# V2_USB.net
KiCad netlist of a schematic drawn in Altium Designer
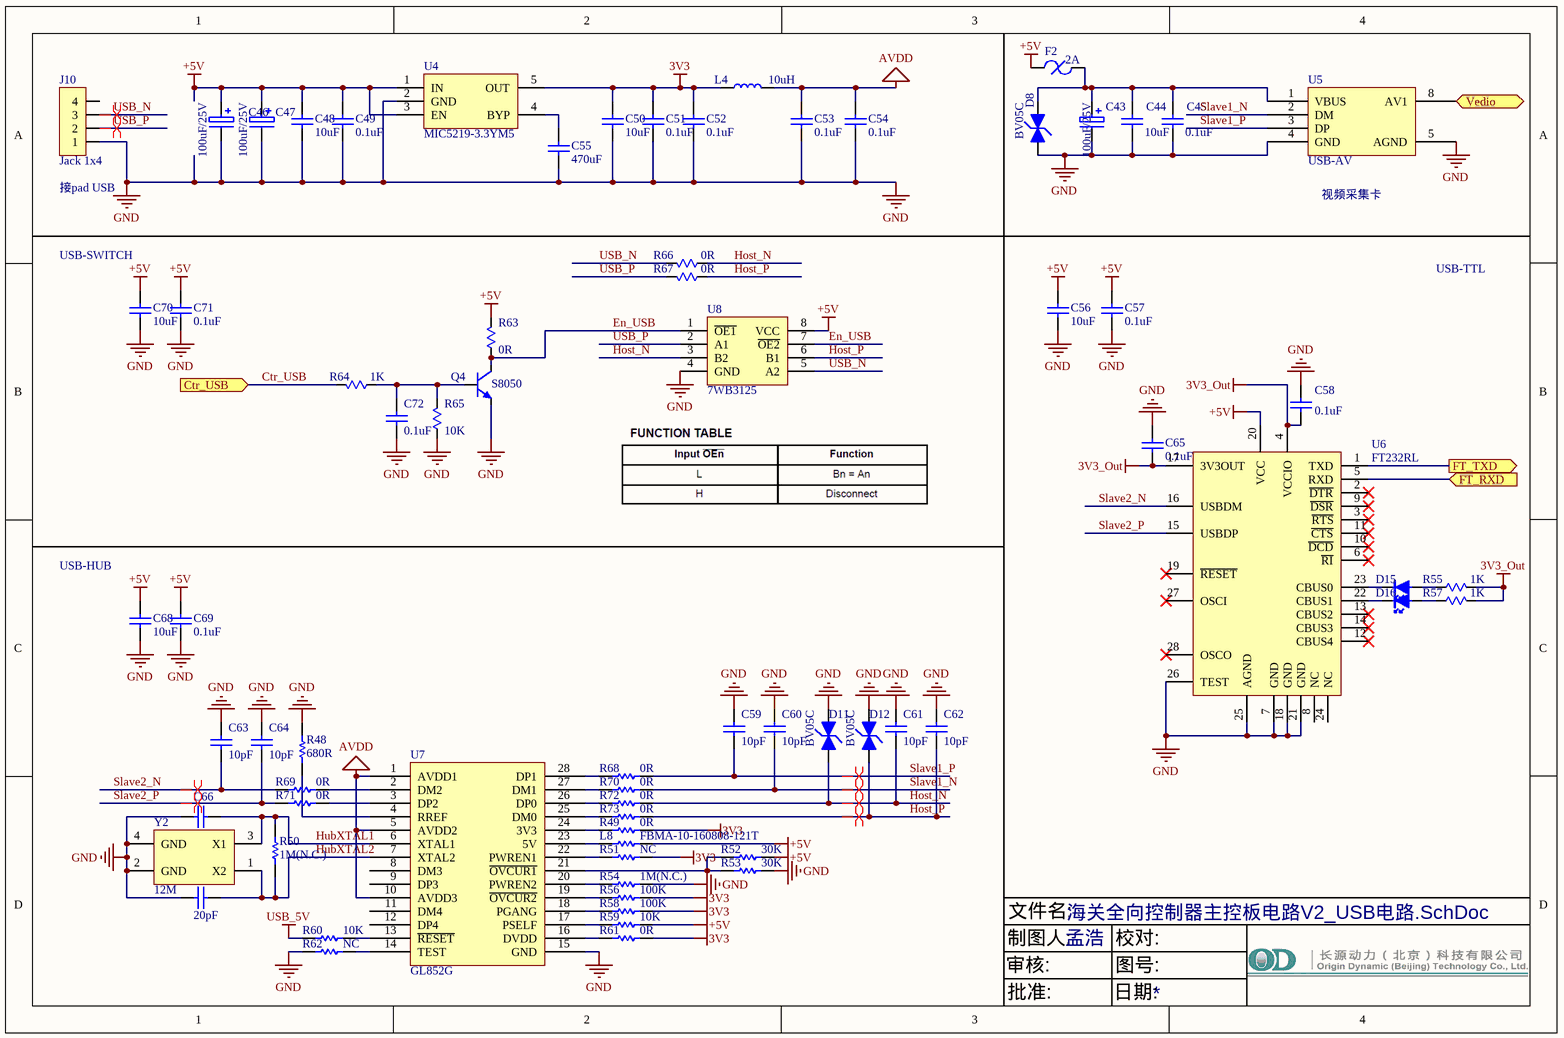
[diagram p0: 海关全向控制器主控板电路V2_USB电路.SchDoc]

(export (version "E")
  (design (tool "Eeschema 10.0.6"))
  (components
    (comp (ref "C43") (value "100uF/25V") (footprint "C7343") (libsource (lib "RLCYDF") (part "Cap Poll")))
    (comp (ref "C44")
      (value "10uF")
      (footprint "C0603")
      (description "CAP")
      (fields (field (name "PUBLISHER") "Altium Limited"))
      (libsource (lib "Passive Components Class") (part "CAP"))
    )
    (comp (ref "C45") (value "0.1uF") (footprint "C0603") (libsource (lib "SMD") (part "Cap Semi")))
    (comp (ref "C46") (value "100uF/25V") (footprint "C7343") (libsource (lib "RLCYDF") (part "Cap Poll")))
    (comp (ref "C47") (value "100uF/25V") (footprint "C7343") (libsource (lib "RLCYDF") (part "Cap Poll")))
    (comp (ref "C48")
      (value "10uF")
      (footprint "C0603")
      (description "CAP")
      (fields (field (name "PUBLISHER") "Altium Limited"))
      (libsource (lib "Passive Components Class") (part "CAP"))
    )
    (comp (ref "C49") (value "0.1uF") (footprint "C0603") (libsource (lib "SMD") (part "Cap Semi")))
    (comp (ref "C50")
      (value "10uF")
      (footprint "C0603")
      (description "CAP")
      (fields (field (name "PUBLISHER") "Altium Limited"))
      (libsource (lib "Passive Components Class") (part "CAP"))
    )
    (comp (ref "C51") (value "0.1uF") (footprint "C0603") (libsource (lib "SMD") (part "Cap Semi")))
    (comp (ref "C52") (value "0.1uF") (footprint "C0603") (libsource (lib "SMD") (part "Cap Semi")))
    (comp (ref "C53") (value "0.1uF") (footprint "C0603") (libsource (lib "SMD") (part "Cap Semi")))
    (comp (ref "C54") (value "0.1uF") (footprint "C0603") (libsource (lib "SMD") (part "Cap Semi")))
    (comp (ref "C55") (value "470uF") (footprint "C0603") (libsource (lib "SMD") (part "Cap Semi")))
    (comp (ref "C56")
      (value "10uF")
      (footprint "C0603")
      (description "CAP")
      (fields (field (name "PUBLISHER") "Altium Limited"))
      (libsource (lib "Passive Components Class") (part "CAP"))
    )
    (comp (ref "C57") (value "0.1uF") (footprint "C0603") (libsource (lib "SMD") (part "Cap Semi")))
    (comp (ref "C58")
      (value "0.1uF")
      (footprint "C0603")
      (description "Capacitor")
      (fields (field (name "PUBLISHER") "Altium Limited"))
      (libsource (lib "Miscellaneous Devices") (part "Cap"))
    )
    (comp (ref "C59") (value "10pF") (footprint "C0603") (libsource (lib "SMD") (part "Cap Semi")))
    (comp (ref "C60") (value "10pF") (footprint "C0603") (libsource (lib "SMD") (part "Cap Semi")))
    (comp (ref "C61") (value "10pF") (footprint "C0603") (libsource (lib "SMD") (part "Cap Semi")))
    (comp (ref "C62") (value "10pF") (footprint "C0603") (libsource (lib "SMD") (part "Cap Semi")))
    (comp (ref "C63") (value "10pF") (footprint "C0603") (libsource (lib "SMD") (part "Cap Semi")))
    (comp (ref "C64") (value "10pF") (footprint "C0603") (libsource (lib "SMD") (part "Cap Semi")))
    (comp (ref "C65") (value "0.1uF") (footprint "C0603") (libsource (lib "SMD") (part "Cap Semi")))
    (comp (ref "C66") (value "20pF") (footprint "C0603") (libsource (lib "SMD") (part "Cap Semi")))
    (comp (ref "C67") (value "20pF") (footprint "C0603") (libsource (lib "SMD") (part "Cap Semi")))
    (comp (ref "C68")
      (value "10uF")
      (footprint "C0603")
      (description "CAP")
      (fields (field (name "PUBLISHER") "Altium Limited"))
      (libsource (lib "Passive Components Class") (part "CAP"))
    )
    (comp (ref "C69") (value "0.1uF") (footprint "C0603") (libsource (lib "SMD") (part "Cap Semi")))
    (comp (ref "C70")
      (value "10uF")
      (footprint "C0603")
      (description "CAP")
      (fields (field (name "PUBLISHER") "Altium Limited"))
      (libsource (lib "Passive Components Class") (part "CAP"))
    )
    (comp (ref "C71") (value "0.1uF") (footprint "C0603") (libsource (lib "SMD") (part "Cap Semi")))
    (comp (ref "C72")
      (value "0.1uF")
      (footprint "C0603")
      (description "CAP")
      (fields (field (name "PUBLISHER") "Altium Limited"))
      (libsource (lib "Passive Components Class") (part "CAP"))
    )
    (comp (ref "D8") (value "BV05C") (footprint "SOD323") (libsource (lib "RLCYDF") (part "Diode-TVS")))
    (comp (ref "D11") (value "BV05C") (footprint "SOD323") (libsource (lib "RLCYDF") (part "Diode-TVS")))
    (comp (ref "D12") (value "BV05C") (footprint "SOD323") (libsource (lib "RLCYDF") (part "Diode-TVS")))
    (comp (ref "D15")
      (value "LED")
      (footprint "LED0603")
      (libsource (lib "Passive Components Class") (part "LED"))
    )
    (comp (ref "D16")
      (value "LED")
      (footprint "LED0603")
      (libsource (lib "Passive Components Class") (part "LED"))
    )
    (comp (ref "F2") (value "2A") (footprint "F1218") (libsource (lib "RLCYDF") (part "Fuse2")))
    (comp (ref "J10")
      (value "Jack 1x4")
      (footprint "ZH-4AWD")
      (description "插座")
      (libsource (lib "Connector") (part "Jack 1x4"))
    )
    (comp (ref "L4") (value "10uH") (footprint "L0603") (libsource (lib "RLCYDF") (part "Inductor")))
    (comp (ref "L8") (value "FBMA-10-160808-121T") (footprint "R0603") (libsource (lib "SMD") (part "Res")))
    (comp (ref "Q4")
      (value "S8050")
      (footprint "SOT-23")
      (description "NPN General Purpose Amplifier")
      (fields (field (name "PUBLISHER") "Altium Limited"))
      (libsource (lib "Bdmc4810") (part "NPN"))
    )
    (comp (ref "R48") (value "680R") (footprint "R0603") (libsource (lib "SMD") (part "Res")))
    (comp (ref "R49") (value "0R") (footprint "R0603") (libsource (lib "SMD") (part "Res")))
    (comp (ref "R50") (value "1M(N.C.)") (footprint "R0603") (libsource (lib "SMD") (part "Res")))
    (comp (ref "R51") (value "NC") (footprint "R0603") (libsource (lib "SMD") (part "Res")))
    (comp (ref "R52") (value "30K") (footprint "R0603") (libsource (lib "SMD") (part "Res")))
    (comp (ref "R53") (value "30K") (footprint "R0603") (libsource (lib "SMD") (part "Res")))
    (comp (ref "R54") (value "1M(N.C.)") (footprint "R0603") (libsource (lib "SMD") (part "Res")))
    (comp (ref "R55")
      (value "1K")
      (footprint "R0603")
      (description "Resistor")
      (fields (field (name "PUBLISHER") "Altium Limited"))
      (libsource (lib "Temp") (part "Res"))
    )
    (comp (ref "R56") (value "100K") (footprint "R0603") (libsource (lib "SMD") (part "Res")))
    (comp (ref "R57")
      (value "1K")
      (footprint "R0603")
      (description "Resistor")
      (fields (field (name "PUBLISHER") "Altium Limited"))
      (libsource (lib "Temp") (part "Res"))
    )
    (comp (ref "R58") (value "100K") (footprint "R0603") (libsource (lib "SMD") (part "Res")))
    (comp (ref "R59") (value "10K") (footprint "R0603") (libsource (lib "SMD") (part "Res")))
    (comp (ref "R60") (value "10K") (footprint "R0603") (libsource (lib "SMD") (part "Res")))
    (comp (ref "R61") (value "0R") (footprint "R0603") (libsource (lib "SMD") (part "Res")))
    (comp (ref "R62") (value "NC") (footprint "R0603") (libsource (lib "SMD") (part "Res")))
    (comp (ref "R63")
      (value "0R")
      (footprint "R0603")
      (description "Resistor")
      (fields (field (name "PUBLISHER") "Altium Limited"))
      (libsource (lib "Temp") (part "Res"))
    )
    (comp (ref "R64")
      (value "1K")
      (footprint "R0603")
      (description "Resistor")
      (fields (field (name "PUBLISHER") "Altium Limited"))
      (libsource (lib "Temp") (part "Res"))
    )
    (comp (ref "R65")
      (value "10K")
      (footprint "R0603")
      (description "Resistor")
      (fields (field (name "PUBLISHER") "Altium Limited"))
      (libsource (lib "Temp") (part "Res"))
    )
    (comp (ref "R66")
      (value "0R")
      (footprint "R0603")
      (description "Resistor")
      (fields (field (name "PUBLISHER") "Altium Limited"))
      (libsource (lib "Temp") (part "Res"))
    )
    (comp (ref "R67")
      (value "0R")
      (footprint "R0603")
      (description "Resistor")
      (fields (field (name "PUBLISHER") "Altium Limited"))
      (libsource (lib "Temp") (part "Res"))
    )
    (comp (ref "R68") (value "0R") (footprint "R0603") (libsource (lib "SMD") (part "Res")))
    (comp (ref "R69") (value "0R") (footprint "R0603") (libsource (lib "SMD") (part "Res")))
    (comp (ref "R70") (value "0R") (footprint "R0603") (libsource (lib "SMD") (part "Res")))
    (comp (ref "R71") (value "0R") (footprint "R0603") (libsource (lib "SMD") (part "Res")))
    (comp (ref "R72") (value "0R") (footprint "R0603") (libsource (lib "SMD") (part "Res")))
    (comp (ref "R73") (value "0R") (footprint "R0603") (libsource (lib "SMD") (part "Res")))
    (comp (ref "U4")
      (value "MIC5219-3.3YM5")
      (footprint "SOT-23-5")
      (libsource (lib "Power") (part "MIC5205"))
    )
    (comp (ref "U5") (value "USB-AV") (footprint "USB-AV") (libsource (lib "Module") (part "USB-AV")))
    (comp (ref "U6")
      (value "FT232RL")
      (footprint "SSOP-28")
      (libsource (lib "海关全向控制器主控板V2") (part "FT232RL"))
    )
    (comp (ref "U7")
      (value "GL852G")
      (footprint "SSOP-28")
      (description "USB 2.0 Low-Power HUB Controller")
      (libsource (lib "chip") (part "GL850G"))
    )
    (comp (ref "U8") (value "7WB3125") (footprint "Micro8") (libsource (lib "chip") (part "7WB3125")))
    (comp (ref "Y2") (value "12M") (footprint "XTAL3225") (libsource (lib "RLCYDF") (part "XTAL3225")))
  )
  (nets
    (net (code "1") (name "+5V") (class "Default")
      (node (ref "C46") (pin "1") (pinfunction "1_1") (pintype "passive"))
      (node (ref "C47") (pin "1") (pinfunction "1_1") (pintype "passive"))
      (node (ref "C48") (pin "1") (pinfunction "1_1") (pintype "passive"))
      (node (ref "C49") (pin "2") (pinfunction "2_2") (pintype "passive"))
      (node (ref "C56") (pin "1") (pinfunction "1_1") (pintype "passive"))
      (node (ref "C57") (pin "2") (pinfunction "2_2") (pintype "passive"))
      (node (ref "C68") (pin "1") (pinfunction "1_1") (pintype "passive"))
      (node (ref "C69") (pin "2") (pinfunction "2_2") (pintype "passive"))
      (node (ref "C70") (pin "1") (pinfunction "1_1") (pintype "passive"))
      (node (ref "C71") (pin "2") (pinfunction "2_2") (pintype "passive"))
      (node (ref "F2") (pin "1") (pinfunction "1_1") (pintype "passive"))
      (node (ref "L8") (pin "2") (pinfunction "2_2") (pintype "passive"))
      (node (ref "R52") (pin "1") (pinfunction "1_1") (pintype "passive"))
      (node (ref "R59") (pin "1") (pinfunction "1_1") (pintype "passive"))
      (node (ref "R63") (pin "1") (pinfunction "1_1") (pintype "passive"))
      (node (ref "U4") (pin "1") (pinfunction "IN_1") (pintype "passive"))
      (node (ref "U4") (pin "3") (pinfunction "EN_3") (pintype "passive"))
      (node (ref "U6") (pin "20") (pinfunction "VCC_20") (pintype "passive"))
      (node (ref "U8") (pin "8") (pinfunction "VCC_8") (pintype "passive"))
    )
    (net (code "2") (name "/Ctr_USB") (class "Default")
      (node (ref "R64") (pin "1") (pinfunction "1_1") (pintype "passive"))
    )
    (net (code "3") (name "/En_USB") (class "Default")
      (node (ref "Q4") (pin "3") (pinfunction "C_3") (pintype "passive"))
      (node (ref "R63") (pin "2") (pinfunction "2_2") (pintype "passive"))
      (node (ref "U8") (pin "1") (pinfunction "~{OE1}_1") (pintype "passive"))
      (node (ref "U8") (pin "7") (pinfunction "~{OE2}_7") (pintype "passive"))
    )
    (net (code "4") (name "/FT_RXD") (class "Default")
      (node (ref "U6") (pin "5") (pinfunction "RXD_5") (pintype "passive"))
    )
    (net (code "5") (name "/FT_TXD") (class "Default")
      (node (ref "U6") (pin "1") (pinfunction "TXD_1") (pintype "passive"))
    )
    (net (code "6") (name "/Host_N") (class "Default")
      (node (ref "C61") (pin "1") (pinfunction "1_1") (pintype "passive"))
      (node (ref "D11") (pin "2") (pinfunction "K_2") (pintype "passive"))
      (node (ref "R66") (pin "2") (pinfunction "2_2") (pintype "passive"))
      (node (ref "R72") (pin "1") (pinfunction "1_1") (pintype "passive"))
      (node (ref "U8") (pin "3") (pinfunction "B2_3") (pintype "passive"))
    )
    (net (code "7") (name "/Host_P") (class "Default")
      (node (ref "C62") (pin "1") (pinfunction "1_1") (pintype "passive"))
      (node (ref "D12") (pin "2") (pinfunction "K_2") (pintype "passive"))
      (node (ref "R67") (pin "2") (pinfunction "2_2") (pintype "passive"))
      (node (ref "R73") (pin "1") (pinfunction "1_1") (pintype "passive"))
      (node (ref "U8") (pin "6") (pinfunction "B1_6") (pintype "passive"))
    )
    (net (code "8") (name "/HubXTAL1") (class "Default")
      (node (ref "C66") (pin "1") (pinfunction "1_1") (pintype "passive"))
      (node (ref "R50") (pin "2") (pinfunction "2_2") (pintype "passive"))
      (node (ref "U7") (pin "6") (pinfunction "XTAL1_6") (pintype "passive"))
      (node (ref "Y2") (pin "3") (pinfunction "X1_3") (pintype "passive"))
    )
    (net (code "9") (name "/HubXTAL2") (class "Default")
      (node (ref "C67") (pin "1") (pinfunction "1_1") (pintype "passive"))
      (node (ref "R50") (pin "1") (pinfunction "1_1") (pintype "passive"))
      (node (ref "U7") (pin "7") (pinfunction "XTAL2_7") (pintype "passive"))
      (node (ref "Y2") (pin "1") (pinfunction "X2_1") (pintype "passive"))
    )
    (net (code "10") (name "/Slave1_N") (class "Default")
      (node (ref "C60") (pin "1") (pinfunction "1_1") (pintype "passive"))
      (node (ref "R70") (pin "1") (pinfunction "1_1") (pintype "passive"))
      (node (ref "U5") (pin "2") (pinfunction "DM_2") (pintype "passive"))
    )
    (net (code "11") (name "/Slave1_P") (class "Default")
      (node (ref "C59") (pin "1") (pinfunction "1_1") (pintype "passive"))
      (node (ref "R68") (pin "1") (pinfunction "1_1") (pintype "passive"))
      (node (ref "U5") (pin "3") (pinfunction "DP_3") (pintype "passive"))
    )
    (net (code "12") (name "/Slave2_N") (class "Default")
      (node (ref "C63") (pin "1") (pinfunction "1_1") (pintype "passive"))
      (node (ref "R69") (pin "2") (pinfunction "2_2") (pintype "passive"))
      (node (ref "U6") (pin "16") (pinfunction "USBDM_16") (pintype "passive"))
    )
    (net (code "13") (name "/Slave2_P") (class "Default")
      (node (ref "C64") (pin "1") (pinfunction "1_1") (pintype "passive"))
      (node (ref "R71") (pin "2") (pinfunction "2_2") (pintype "passive"))
      (node (ref "U6") (pin "15") (pinfunction "USBDP_15") (pintype "passive"))
    )
    (net (code "14") (name "/USB_N") (class "Default")
      (node (ref "J10") (pin "3") (pinfunction "3_3") (pintype "passive"))
      (node (ref "R66") (pin "1") (pinfunction "1_1") (pintype "passive"))
      (node (ref "U8") (pin "5") (pinfunction "A2_5") (pintype "passive"))
    )
    (net (code "15") (name "/USB_P") (class "Default")
      (node (ref "J10") (pin "2") (pinfunction "2_2") (pintype "passive"))
      (node (ref "R67") (pin "1") (pinfunction "1_1") (pintype "passive"))
      (node (ref "U8") (pin "2") (pinfunction "A1_2") (pintype "passive"))
    )
    (net (code "16") (name "/Vedio") (class "Default")
      (node (ref "U5") (pin "8") (pinfunction "AV1_8") (pintype "passive"))
    )
    (net (code "17") (name "3V3") (class "Default")
      (node (ref "C50") (pin "1") (pinfunction "1_1") (pintype "passive"))
      (node (ref "C51") (pin "2") (pinfunction "2_2") (pintype "passive"))
      (node (ref "C52") (pin "2") (pinfunction "2_2") (pintype "passive"))
      (node (ref "L4") (pin "1") (pinfunction "1_1") (pintype "passive"))
      (node (ref "R49") (pin "1") (pinfunction "1_1") (pintype "passive"))
      (node (ref "R51") (pin "1") (pinfunction "1_1") (pintype "passive"))
      (node (ref "R56") (pin "1") (pinfunction "1_1") (pintype "passive"))
      (node (ref "R58") (pin "1") (pinfunction "1_1") (pintype "passive"))
      (node (ref "R61") (pin "1") (pinfunction "1_1") (pintype "passive"))
      (node (ref "U4") (pin "5") (pinfunction "OUT_5") (pintype "passive"))
    )
    (net (code "18") (name "3V3_Out") (class "Default")
      (node (ref "C58") (pin "2") (pinfunction "2_2") (pintype "passive"))
      (node (ref "C65") (pin "1") (pinfunction "1_1") (pintype "passive"))
      (node (ref "R55") (pin "1") (pinfunction "1_1") (pintype "passive"))
      (node (ref "R57") (pin "1") (pinfunction "1_1") (pintype "passive"))
      (node (ref "U6") (pin "17") (pinfunction "3V3OUT_17") (pintype "passive"))
      (node (ref "U6") (pin "4") (pinfunction "VCCIO_4") (pintype "passive"))
    )
    (net (code "19") (name "AVDD") (class "Default")
      (node (ref "C53") (pin "2") (pinfunction "2_2") (pintype "passive"))
      (node (ref "C54") (pin "2") (pinfunction "2_2") (pintype "passive"))
      (node (ref "L4") (pin "2") (pinfunction "2_2") (pintype "passive"))
      (node (ref "U7") (pin "1") (pinfunction "AVDD1_1") (pintype "passive"))
      (node (ref "U7") (pin "10") (pinfunction "AVDD3_10") (pintype "passive"))
      (node (ref "U7") (pin "5") (pinfunction "AVDD2_5") (pintype "passive"))
    )
    (net (code "20") (name "GND") (class "Default")
      (node (ref "C43") (pin "2") (pinfunction "2_2") (pintype "passive"))
      (node (ref "C44") (pin "2") (pinfunction "2_2") (pintype "passive"))
      (node (ref "C45") (pin "1") (pinfunction "1_1") (pintype "passive"))
      (node (ref "C46") (pin "2") (pinfunction "2_2") (pintype "passive"))
      (node (ref "C47") (pin "2") (pinfunction "2_2") (pintype "passive"))
      (node (ref "C48") (pin "2") (pinfunction "2_2") (pintype "passive"))
      (node (ref "C49") (pin "1") (pinfunction "1_1") (pintype "passive"))
      (node (ref "C50") (pin "2") (pinfunction "2_2") (pintype "passive"))
      (node (ref "C51") (pin "1") (pinfunction "1_1") (pintype "passive"))
      (node (ref "C52") (pin "1") (pinfunction "1_1") (pintype "passive"))
      (node (ref "C53") (pin "1") (pinfunction "1_1") (pintype "passive"))
      (node (ref "C54") (pin "1") (pinfunction "1_1") (pintype "passive"))
      (node (ref "C55") (pin "1") (pinfunction "1_1") (pintype "passive"))
      (node (ref "C56") (pin "2") (pinfunction "2_2") (pintype "passive"))
      (node (ref "C57") (pin "1") (pinfunction "1_1") (pintype "passive"))
      (node (ref "C58") (pin "1") (pinfunction "1_1") (pintype "passive"))
      (node (ref "C59") (pin "2") (pinfunction "2_2") (pintype "passive"))
      (node (ref "C60") (pin "2") (pinfunction "2_2") (pintype "passive"))
      (node (ref "C61") (pin "2") (pinfunction "2_2") (pintype "passive"))
      (node (ref "C62") (pin "2") (pinfunction "2_2") (pintype "passive"))
      (node (ref "C63") (pin "2") (pinfunction "2_2") (pintype "passive"))
      (node (ref "C64") (pin "2") (pinfunction "2_2") (pintype "passive"))
      (node (ref "C65") (pin "2") (pinfunction "2_2") (pintype "passive"))
      (node (ref "C66") (pin "2") (pinfunction "2_2") (pintype "passive"))
      (node (ref "C67") (pin "2") (pinfunction "2_2") (pintype "passive"))
      (node (ref "C68") (pin "2") (pinfunction "2_2") (pintype "passive"))
      (node (ref "C69") (pin "1") (pinfunction "1_1") (pintype "passive"))
      (node (ref "C70") (pin "2") (pinfunction "2_2") (pintype "passive"))
      (node (ref "C71") (pin "1") (pinfunction "1_1") (pintype "passive"))
      (node (ref "C72") (pin "1") (pinfunction "1_1") (pintype "passive"))
      (node (ref "D11") (pin "1") (pinfunction "A_1") (pintype "passive"))
      (node (ref "D12") (pin "1") (pinfunction "A_1") (pintype "passive"))
      (node (ref "D8") (pin "2") (pinfunction "K_2") (pintype "passive"))
      (node (ref "J10") (pin "1") (pinfunction "1_1") (pintype "passive"))
      (node (ref "Q4") (pin "2") (pinfunction "E_2") (pintype "passive"))
      (node (ref "R48") (pin "2") (pinfunction "2_2") (pintype "passive"))
      (node (ref "R53") (pin "1") (pinfunction "1_1") (pintype "passive"))
      (node (ref "R54") (pin "1") (pinfunction "1_1") (pintype "passive"))
      (node (ref "R62") (pin "2") (pinfunction "2_2") (pintype "passive"))
      (node (ref "R65") (pin "2") (pinfunction "2_2") (pintype "passive"))
      (node (ref "U4") (pin "2") (pinfunction "GND_2") (pintype "passive"))
      (node (ref "U5") (pin "4") (pinfunction "GND_4") (pintype "passive"))
      (node (ref "U5") (pin "5") (pinfunction "AGND_5") (pintype "passive"))
      (node (ref "U6") (pin "18") (pinfunction "GND_18") (pintype "passive"))
      (node (ref "U6") (pin "21") (pinfunction "GND_21") (pintype "passive"))
      (node (ref "U6") (pin "25") (pinfunction "AGND_25") (pintype "passive"))
      (node (ref "U6") (pin "26") (pinfunction "TEST_26") (pintype "passive"))
      (node (ref "U6") (pin "7") (pinfunction "GND_7") (pintype "passive"))
      (node (ref "U7") (pin "15") (pinfunction "GND_15") (pintype "passive"))
      (node (ref "U8") (pin "4") (pinfunction "GND_4") (pintype "passive"))
      (node (ref "Y2") (pin "2") (pinfunction "GND_2") (pintype "passive"))
      (node (ref "Y2") (pin "4") (pinfunction "GND_4") (pintype "passive"))
    )
    (net (code "21") (name "Net-(D8-A)") (class "Default")
      (node (ref "C43") (pin "1") (pinfunction "1_1") (pintype "passive"))
      (node (ref "C44") (pin "1") (pinfunction "1_1") (pintype "passive"))
      (node (ref "C45") (pin "2") (pinfunction "2_2") (pintype "passive"))
      (node (ref "D8") (pin "1") (pinfunction "A_1") (pintype "passive"))
      (node (ref "F2") (pin "2") (pinfunction "2_2") (pintype "passive"))
      (node (ref "U5") (pin "1") (pinfunction "VBUS_1") (pintype "passive"))
    )
    (net (code "22") (name "Net-(D15-A)") (class "Default")
      (node (ref "D15") (pin "1") (pinfunction "A_1") (pintype "passive"))
      (node (ref "R55") (pin "2") (pinfunction "2_2") (pintype "passive"))
    )
    (net (code "23") (name "Net-(D15-K)") (class "Default")
      (node (ref "D15") (pin "2") (pinfunction "K_2") (pintype "passive"))
      (node (ref "U6") (pin "23") (pinfunction "CBUS0_23") (pintype "passive"))
    )
    (net (code "24") (name "Net-(D16-A)") (class "Default")
      (node (ref "D16") (pin "1") (pinfunction "A_1") (pintype "passive"))
      (node (ref "R57") (pin "2") (pinfunction "2_2") (pintype "passive"))
    )
    (net (code "25") (name "Net-(D16-K)") (class "Default")
      (node (ref "D16") (pin "2") (pinfunction "K_2") (pintype "passive"))
      (node (ref "U6") (pin "22") (pinfunction "CBUS1_22") (pintype "passive"))
    )
    (net (code "26") (name "Net-(Q4-B)") (class "Default")
      (node (ref "C72") (pin "2") (pinfunction "2_2") (pintype "passive"))
      (node (ref "Q4") (pin "1") (pinfunction "B_1") (pintype "passive"))
      (node (ref "R64") (pin "2") (pinfunction "2_2") (pintype "passive"))
      (node (ref "R65") (pin "1") (pinfunction "1_1") (pintype "passive"))
    )
    (net (code "27") (name "Net-(U4-BYP)") (class "Default")
      (node (ref "C55") (pin "2") (pinfunction "2_2") (pintype "passive"))
      (node (ref "U4") (pin "4") (pinfunction "BYP_4") (pintype "passive"))
    )
    (net (code "28") (name "Net-(U7-3V3)") (class "Default")
      (node (ref "R49") (pin "2") (pinfunction "2_2") (pintype "passive"))
      (node (ref "U7") (pin "24") (pinfunction "3V3_24") (pintype "passive"))
    )
    (net (code "29") (name "Net-(U7-5V)") (class "Default")
      (node (ref "L8") (pin "1") (pinfunction "1_1") (pintype "passive"))
      (node (ref "U7") (pin "23") (pinfunction "5V_23") (pintype "passive"))
    )
    (net (code "30") (name "Net-(U7-DM0)") (class "Default")
      (node (ref "R73") (pin "2") (pinfunction "2_2") (pintype "passive"))
      (node (ref "U7") (pin "25") (pinfunction "DM0_25") (pintype "passive"))
    )
    (net (code "31") (name "Net-(U7-DM1)") (class "Default")
      (node (ref "R70") (pin "2") (pinfunction "2_2") (pintype "passive"))
      (node (ref "U7") (pin "27") (pinfunction "DM1_27") (pintype "passive"))
    )
    (net (code "32") (name "Net-(U7-DM2)") (class "Default")
      (node (ref "R69") (pin "1") (pinfunction "1_1") (pintype "passive"))
      (node (ref "U7") (pin "2") (pinfunction "DM2_2") (pintype "passive"))
    )
    (net (code "33") (name "Net-(U7-DP0)") (class "Default")
      (node (ref "R72") (pin "2") (pinfunction "2_2") (pintype "passive"))
      (node (ref "U7") (pin "26") (pinfunction "DP0_26") (pintype "passive"))
    )
    (net (code "34") (name "Net-(U7-DP1)") (class "Default")
      (node (ref "R68") (pin "2") (pinfunction "2_2") (pintype "passive"))
      (node (ref "U7") (pin "28") (pinfunction "DP1_28") (pintype "passive"))
    )
    (net (code "35") (name "Net-(U7-DP2)") (class "Default")
      (node (ref "R71") (pin "1") (pinfunction "1_1") (pintype "passive"))
      (node (ref "U7") (pin "3") (pinfunction "DP2_3") (pintype "passive"))
    )
    (net (code "36") (name "Net-(U7-DVDD)") (class "Default")
      (node (ref "R61") (pin "2") (pinfunction "2_2") (pintype "passive"))
      (node (ref "U7") (pin "16") (pinfunction "DVDD_16") (pintype "passive"))
    )
    (net (code "37") (name "Net-(U7-PGANG)") (class "Default")
      (node (ref "R58") (pin "2") (pinfunction "2_2") (pintype "passive"))
      (node (ref "U7") (pin "18") (pinfunction "PGANG_18") (pintype "passive"))
    )
    (net (code "38") (name "Net-(U7-PSELF)") (class "Default")
      (node (ref "R59") (pin "2") (pinfunction "2_2") (pintype "passive"))
      (node (ref "U7") (pin "17") (pinfunction "PSELF_17") (pintype "passive"))
    )
    (net (code "39") (name "Net-(U7-PWREN1)") (class "Default")
      (node (ref "R51") (pin "2") (pinfunction "2_2") (pintype "passive"))
      (node (ref "U7") (pin "22") (pinfunction "PWREN1_22") (pintype "passive"))
    )
    (net (code "40") (name "Net-(U7-PWREN2)") (class "Default")
      (node (ref "R54") (pin "2") (pinfunction "2_2") (pintype "passive"))
      (node (ref "U7") (pin "20") (pinfunction "PWREN2_20") (pintype "passive"))
    )
    (net (code "41") (name "Net-(U7-RREF)") (class "Default")
      (node (ref "R48") (pin "1") (pinfunction "1_1") (pintype "passive"))
      (node (ref "U7") (pin "4") (pinfunction "RREF_4") (pintype "passive"))
    )
    (net (code "42") (name "Net-(U7-TEST)") (class "Default")
      (node (ref "R62") (pin "1") (pinfunction "1_1") (pintype "passive"))
      (node (ref "U7") (pin "14") (pinfunction "TEST_14") (pintype "passive"))
    )
    (net (code "43") (name "Net-(U7-~{OVCUR1})") (class "Default")
      (node (ref "R52") (pin "2") (pinfunction "2_2") (pintype "passive"))
      (node (ref "R53") (pin "2") (pinfunction "2_2") (pintype "passive"))
      (node (ref "U7") (pin "21") (pinfunction "~{OVCUR1}_21") (pintype "passive"))
    )
    (net (code "44") (name "Net-(U7-~{OVCUR2})") (class "Default")
      (node (ref "R56") (pin "2") (pinfunction "2_2") (pintype "passive"))
      (node (ref "U7") (pin "19") (pinfunction "~{OVCUR2}_19") (pintype "passive"))
    )
    (net (code "45") (name "Net-(U7-~{RESET})") (class "Default")
      (node (ref "R60") (pin "1") (pinfunction "1_1") (pintype "passive"))
      (node (ref "U7") (pin "13") (pinfunction "~{RESET}_13") (pintype "passive"))
    )
    (net (code "46") (name "USB_5V") (class "Default")
      (node (ref "R60") (pin "2") (pinfunction "2_2") (pintype "passive"))
    )
    (net (code "47") (name "unconnected-(J10-Pad4)") (class "Default")
      (node (ref "J10") (pin "4") (pinfunction "4_4") (pintype "passive"))
    )
    (net (code "48") (name "unconnected-(U6-CBUS2-Pad13)") (class "Default")
      (node (ref "U6") (pin "13") (pinfunction "CBUS2_13") (pintype "passive+no_connect"))
    )
    (net (code "49") (name "unconnected-(U6-CBUS3-Pad14)") (class "Default")
      (node (ref "U6") (pin "14") (pinfunction "CBUS3_14") (pintype "passive+no_connect"))
    )
    (net (code "50") (name "unconnected-(U6-CBUS4-Pad12)") (class "Default")
      (node (ref "U6") (pin "12") (pinfunction "CBUS4_12") (pintype "passive+no_connect"))
    )
    (net (code "51") (name "unconnected-(U6-NC-Pad8)") (class "Default")
      (node (ref "U6") (pin "8") (pinfunction "NC_8") (pintype "passive"))
    )
    (net (code "52") (name "unconnected-(U6-NC-Pad24)") (class "Default")
      (node (ref "U6") (pin "24") (pinfunction "NC_24") (pintype "passive"))
    )
    (net (code "53") (name "unconnected-(U6-OSCI-Pad27)") (class "Default")
      (node (ref "U6") (pin "27") (pinfunction "OSCI_27") (pintype "passive+no_connect"))
    )
    (net (code "54") (name "unconnected-(U6-OSCO-Pad28)") (class "Default")
      (node (ref "U6") (pin "28") (pinfunction "OSCO_28") (pintype "passive+no_connect"))
    )
    (net (code "55") (name "unconnected-(U6-~{CTS}-Pad11)") (class "Default")
      (node (ref "U6") (pin "11") (pinfunction "~{CTS}_11") (pintype "passive+no_connect"))
    )
    (net (code "56") (name "unconnected-(U6-~{DCD}-Pad10)") (class "Default")
      (node (ref "U6") (pin "10") (pinfunction "~{DCD}_10") (pintype "passive+no_connect"))
    )
    (net (code "57") (name "unconnected-(U6-~{DSR}-Pad9)") (class "Default")
      (node (ref "U6") (pin "9") (pinfunction "~{DSR}_9") (pintype "passive+no_connect"))
    )
    (net (code "58") (name "unconnected-(U6-~{DTR}-Pad2)") (class "Default")
      (node (ref "U6") (pin "2") (pinfunction "~{DTR}_2") (pintype "passive+no_connect"))
    )
    (net (code "59") (name "unconnected-(U6-~{RESET}-Pad19)") (class "Default")
      (node (ref "U6") (pin "19") (pinfunction "~{RESET}_19") (pintype "passive+no_connect"))
    )
    (net (code "60") (name "unconnected-(U6-~{RI}-Pad6)") (class "Default")
      (node (ref "U6") (pin "6") (pinfunction "~{RI}_6") (pintype "passive+no_connect"))
    )
    (net (code "61") (name "unconnected-(U6-~{RTS}-Pad3)") (class "Default")
      (node (ref "U6") (pin "3") (pinfunction "~{RTS}_3") (pintype "passive+no_connect"))
    )
    (net (code "62") (name "unconnected-(U7-DM3-Pad8)") (class "Default")
      (node (ref "U7") (pin "8") (pinfunction "DM3_8") (pintype "passive"))
    )
    (net (code "63") (name "unconnected-(U7-DM4-Pad11)") (class "Default")
      (node (ref "U7") (pin "11") (pinfunction "DM4_11") (pintype "passive"))
    )
    (net (code "64") (name "unconnected-(U7-DP3-Pad9)") (class "Default")
      (node (ref "U7") (pin "9") (pinfunction "DP3_9") (pintype "passive"))
    )
    (net (code "65") (name "unconnected-(U7-DP4-Pad12)") (class "Default")
      (node (ref "U7") (pin "12") (pinfunction "DP4_12") (pintype "passive"))
    )
  )
)
